# schematic.net
KiCad netlist of a schematic drawn in Altium Designer
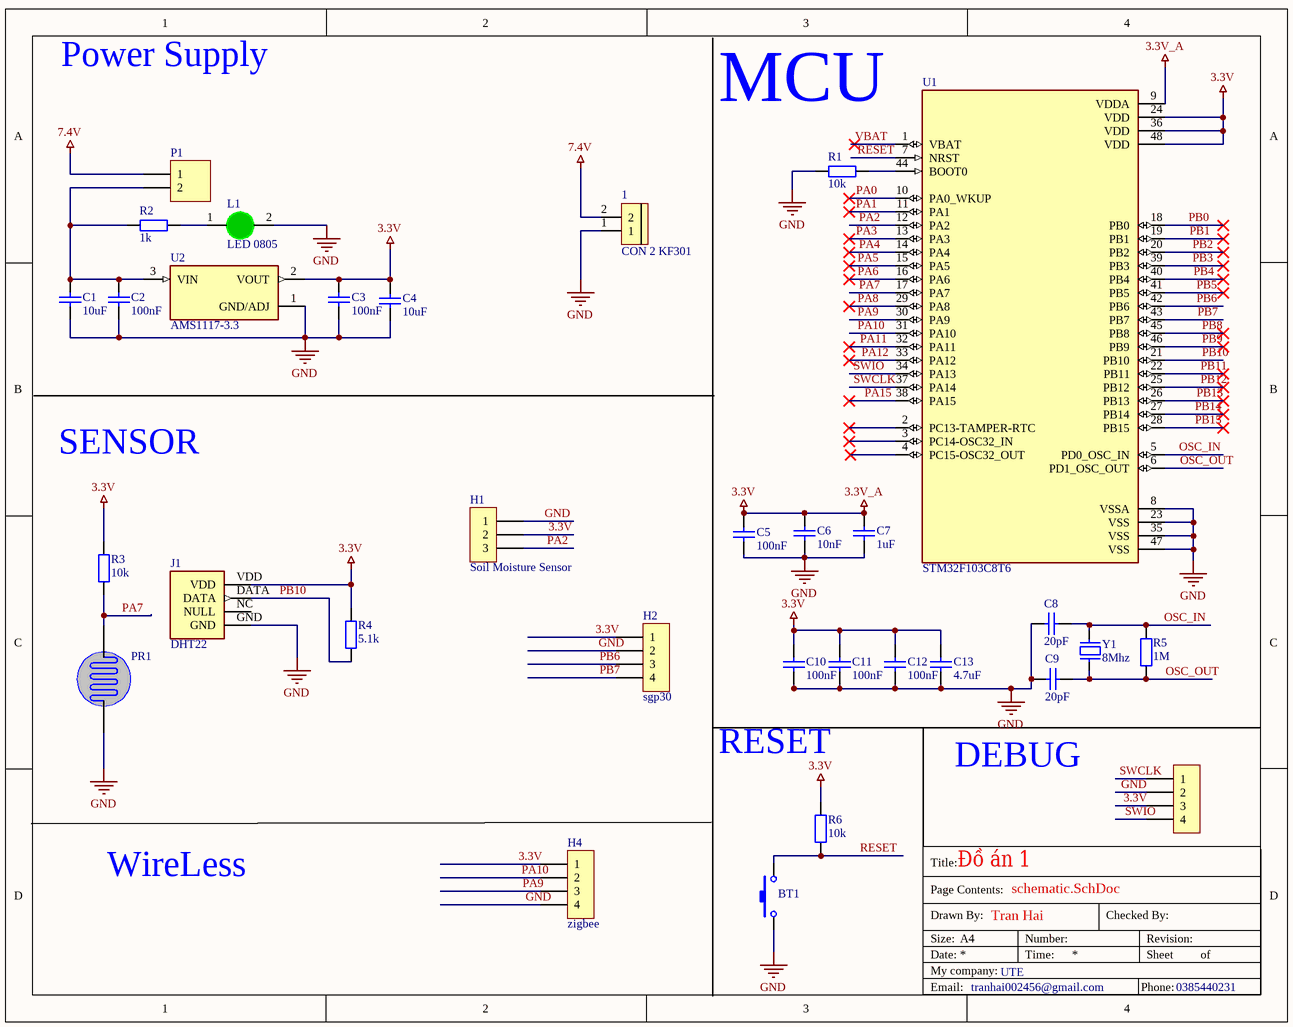
[diagram p0: schematic.SchDoc]

(export (version "E")
  (design (tool "Eeschema 10.0.6"))
  (components
    (comp (ref "1")
      (value "CON 2 KF301")
      (footprint "Con 2 KF301 5.08")
      (description "Cắm")
      (libsource (lib "Altium_Lib_by_KhueNguyenCreator") (part "CON 2 KF301"))
    )
    (comp (ref "BT1")
      (value "Nut Nhan 2 Chan SMD 3x6x2.5")
      (footprint "Nut Nhan 2 Chan SMD 3x6x2.5")
      (libsource (lib "Altium_Lib_by_KhueNguyenCreator") (part "Nut Nhan 2 Chan SMD 3x6x2.5"))
    )
    (comp (ref "C1")
      (value "10uF")
      (footprint "Tu 0805")
      (description "Dán")
      (libsource (lib "Altium_Lib_by_KhueNguyenCreator") (part "Tu 0805 200pF 50V 10%"))
    )
    (comp (ref "C2")
      (value "100nF")
      (footprint "Tu 0805")
      (description "Dán")
      (libsource (lib "Altium_Lib_by_KhueNguyenCreator") (part "Tu 0805 200pF 50V 10%"))
    )
    (comp (ref "C3")
      (value "100nF")
      (footprint "Tu 0805")
      (description "Dán")
      (libsource (lib "Altium_Lib_by_KhueNguyenCreator") (part "Tu 0805 200pF 50V 10%"))
    )
    (comp (ref "C4")
      (value "10uF")
      (footprint "Tu 0805")
      (description "Dán")
      (libsource (lib "Altium_Lib_by_KhueNguyenCreator") (part "Tu 0805 200pF 50V 10%"))
    )
    (comp (ref "C5")
      (value "100nF")
      (footprint "tu 0805")
      (description "Dán")
      (libsource (lib "Altium_Lib_by_KhueNguyenCreator") (part "Tu 0805 101 50V 20%"))
    )
    (comp (ref "C6")
      (value "10nF")
      (footprint "tu 0805")
      (description "Dán")
      (libsource (lib "Altium_Lib_by_KhueNguyenCreator") (part "Tu 0805 101 50V 20%"))
    )
    (comp (ref "C7")
      (value "1uF")
      (footprint "tu 0805")
      (description "Dán")
      (libsource (lib "Altium_Lib_by_KhueNguyenCreator") (part "Tu 0805 101 50V 20%"))
    )
    (comp (ref "C8")
      (value "20pF")
      (footprint "tu 0805")
      (description "Dán")
      (libsource (lib "Altium_Lib_by_KhueNguyenCreator") (part "Tu 0805 101 50V 20%"))
    )
    (comp (ref "C9")
      (value "20pF")
      (footprint "tu 0805")
      (description "Dán")
      (libsource (lib "Altium_Lib_by_KhueNguyenCreator") (part "Tu 0805 101 50V 20%"))
    )
    (comp (ref "C10")
      (value "100nF")
      (footprint "tu 0805")
      (description "Dán")
      (libsource (lib "") (part "Tu 0805 101 50V 20%_1"))
    )
    (comp (ref "C11")
      (value "100nF")
      (footprint "tu 0805")
      (description "Dán")
      (libsource (lib "") (part "Tu 0805 101 50V 20%_1"))
    )
    (comp (ref "C12")
      (value "100nF")
      (footprint "tu 0805")
      (description "Dán")
      (libsource (lib "") (part "Tu 0805 101 50V 20%_1"))
    )
    (comp (ref "C13")
      (value "4.7uF")
      (footprint "tu 0805")
      (description "Dán")
      (libsource (lib "") (part "Tu 0805 101 50V 20%_1"))
    )
    (comp (ref "H1")
      (value "Soil Moisture Sensor")
      (footprint "XH2.54M-3")
      (description "Cắm")
      (libsource (lib "Altium_Lib_by_KhueNguyenCreator") (part "Header 3P 2.54 Duc Thang"))
    )
    (comp (ref "H2")
      (value "sgp30")
      (footprint "XH2.54M-4")
      (description "Cắm")
      (libsource (lib "Altium_Lib_by_KhueNguyenCreator") (part "Header 4P 2.54 Duc Thang"))
    )
    (comp (ref "H3")
      (value "Header 4P 2.54 Duc Thang")
      (footprint "XH2.54M-4")
      (description "Cắm")
      (libsource (lib "Altium_Lib_by_KhueNguyenCreator") (part "Header 4P 2.54 Duc Thang"))
    )
    (comp (ref "H4")
      (value "zigbee")
      (footprint "XH2.54M-4")
      (description "Cắm")
      (libsource (lib "Altium_Lib_by_KhueNguyenCreator") (part "Header 4P 2.54 Duc Thang"))
    )
    (comp (ref "J1")
      (value "DHT22")
      (footprint "DHT22")
      (description "Capacitive-type humidity and temperature module/sensor")
      (fields (field (name "MF") "Aosong Electronics"))
      (libsource (lib "DHT22") (part "DHT22"))
    )
    (comp (ref "L1")
      (value "LED 0805")
      (footprint "LED-0805-Green")
      (description "Dán")
      (libsource (lib "Altium_Lib_by_KhueNguyenCreator") (part "LED 0805 Xanh La"))
    )
    (comp (ref "P1")
      (value "Header 2")
      (footprint "HDR1X2")
      (description "Header, 2-Pin")
      (fields (field (name "PUBLISHER") "Altium Limited"))
      (libsource (lib "Library AL") (part "Header 2"))
    )
    (comp (ref "PR1")
      (value "Quang Tro")
      (footprint "Quang Tro")
      (description "Photoresistor")
      (fields (field (name "CREATOR") "Bien Nguyen"))
      (libsource (lib "Altium_Lib_by_KhueNguyenCreator") (part "Quang Tro"))
    )
    (comp (ref "R1")
      (value "10k")
      (footprint "tro smd 0805")
      (description "Dán")
      (libsource (lib "Altium_Lib_by_KhueNguyenCreator") (part "Tro 0805 1% 10k"))
    )
    (comp (ref "R2")
      (value "1k")
      (footprint "tro smd 0805")
      (description "Dán")
      (libsource (lib "Altium_Lib_by_KhueNguyenCreator") (part "Tro 0805 1% 10k"))
    )
    (comp (ref "R3")
      (value "10k")
      (footprint "tro smd 0805")
      (description "Dán")
      (libsource (lib "Altium_Lib_by_KhueNguyenCreator") (part "Tro 0805 1% 10k"))
    )
    (comp (ref "R4")
      (value "5.1k")
      (footprint "tro smd 0805")
      (description "Dán")
      (libsource (lib "Altium_Lib_by_KhueNguyenCreator") (part "Tro 0805 1% 10k"))
    )
    (comp (ref "R5")
      (value "1M")
      (footprint "tro smd 0805")
      (description "Dán")
      (libsource (lib "Altium_Lib_by_KhueNguyenCreator") (part "Tro 0805 1% 10k"))
    )
    (comp (ref "R6")
      (value "10k")
      (footprint "tro smd 0805")
      (description "Dán")
      (libsource (lib "Altium_Lib_by_KhueNguyenCreator") (part "Tro 0805 1% 10k"))
    )
    (comp (ref "U1")
      (value "STM32F103C8T6")
      (footprint "QFP50P900X900X160-48N")
      (description "ARM® Cortex®-M3 STM32F1 Microcontroller IC 32-Bit 72MHz 64KB (64K x 8) FLASH 48-LQFP (7x7)")
      (fields (field (name "MF") "STMicroelectronics"))
      (libsource (lib "STM32F103C8T6") (part "STM32F103C8T6"))
    )
    (comp (ref "U2")
      (value "AMS1117-3.3")
      (footprint "SOT229P700X180-4N")
      (description "Sot223/Pkg 1-Amp 3.3-Volt Low Drop Out Voltage Regulatator")
      (fields (field (name "MF") "Advanced Monolithic Systems"))
      (libsource (lib "AMS1117-3.3") (part "AMS1117-3.3"))
    )
    (comp (ref "Y1")
      (value "8Mhz")
      (footprint "Thach Anh 2 chan cam")
      (description "Crystal For all Crystal 2pin.")
      (libsource (lib "Altium_Lib_by_KhueNguyenCreator") (part "Thach Anh 2 chan Cam"))
    )
  )
  (nets
    (net (code "1") (name "/OSC_IN") (class "Default")
      (node (ref "C8") (pin "1") (pinfunction "1_1") (pintype "passive"))
      (node (ref "R5") (pin "2") (pinfunction "2_2") (pintype "passive"))
      (node (ref "U1") (pin "5") (pinfunction "PD0_OSC_IN_5") (pintype "bidirectional"))
      (node (ref "Y1") (pin "2") (pinfunction "2_2") (pintype "passive"))
    )
    (net (code "2") (name "/OSC_OUT") (class "Default")
      (node (ref "C9") (pin "1") (pinfunction "1_1") (pintype "passive"))
      (node (ref "R5") (pin "1") (pinfunction "1_1") (pintype "passive"))
      (node (ref "U1") (pin "6") (pinfunction "PD1_OSC_OUT_6") (pintype "bidirectional"))
      (node (ref "Y1") (pin "1") (pinfunction "1_1") (pintype "passive"))
    )
    (net (code "3") (name "/PA0") (class "Default")
      (node (ref "U1") (pin "10") (pinfunction "PA0_WKUP_10") (pintype "bidirectional+no_connect"))
    )
    (net (code "4") (name "/PA1") (class "Default")
      (node (ref "U1") (pin "11") (pinfunction "PA1_11") (pintype "bidirectional+no_connect"))
    )
    (net (code "5") (name "/PA2") (class "Default")
      (node (ref "H1") (pin "3") (pinfunction "3_3") (pintype "passive"))
      (node (ref "U1") (pin "12") (pinfunction "PA2_12") (pintype "bidirectional"))
    )
    (net (code "6") (name "/PA3") (class "Default")
      (node (ref "U1") (pin "13") (pinfunction "PA3_13") (pintype "bidirectional+no_connect"))
    )
    (net (code "7") (name "/PA4") (class "Default")
      (node (ref "U1") (pin "14") (pinfunction "PA4_14") (pintype "bidirectional+no_connect"))
    )
    (net (code "8") (name "/PA5") (class "Default")
      (node (ref "U1") (pin "15") (pinfunction "PA5_15") (pintype "bidirectional+no_connect"))
    )
    (net (code "9") (name "/PA6") (class "Default")
      (node (ref "U1") (pin "16") (pinfunction "PA6_16") (pintype "bidirectional+no_connect"))
    )
    (net (code "10") (name "/PA7") (class "Default")
      (node (ref "PR1") (pin "1") (pinfunction "1_1") (pintype "passive"))
      (node (ref "R3") (pin "1") (pinfunction "1_1") (pintype "passive"))
      (node (ref "U1") (pin "17") (pinfunction "PA7_17") (pintype "bidirectional"))
    )
    (net (code "11") (name "/PA8") (class "Default")
      (node (ref "U1") (pin "29") (pinfunction "PA8_29") (pintype "bidirectional+no_connect"))
    )
    (net (code "12") (name "/PA9") (class "Default")
      (node (ref "H4") (pin "3") (pinfunction "3_3") (pintype "passive"))
      (node (ref "U1") (pin "30") (pinfunction "PA9_30") (pintype "bidirectional"))
    )
    (net (code "13") (name "/PA10") (class "Default")
      (node (ref "H4") (pin "2") (pinfunction "2_2") (pintype "passive"))
      (node (ref "U1") (pin "31") (pinfunction "PA10_31") (pintype "bidirectional"))
    )
    (net (code "14") (name "/PA11") (class "Default")
      (node (ref "U1") (pin "32") (pinfunction "PA11_32") (pintype "bidirectional+no_connect"))
    )
    (net (code "15") (name "/PA12") (class "Default")
      (node (ref "U1") (pin "33") (pinfunction "PA12_33") (pintype "bidirectional+no_connect"))
    )
    (net (code "16") (name "/PA15") (class "Default")
      (node (ref "U1") (pin "38") (pinfunction "PA15_38") (pintype "bidirectional+no_connect"))
    )
    (net (code "17") (name "/PB0") (class "Default")
      (node (ref "U1") (pin "18") (pinfunction "PB0_18") (pintype "bidirectional+no_connect"))
    )
    (net (code "18") (name "/PB1") (class "Default")
      (node (ref "U1") (pin "19") (pinfunction "PB1_19") (pintype "bidirectional+no_connect"))
    )
    (net (code "19") (name "/PB2") (class "Default")
      (node (ref "U1") (pin "20") (pinfunction "PB2_20") (pintype "bidirectional+no_connect"))
    )
    (net (code "20") (name "/PB3") (class "Default")
      (node (ref "U1") (pin "39") (pinfunction "PB3_39") (pintype "bidirectional+no_connect"))
    )
    (net (code "21") (name "/PB4") (class "Default")
      (node (ref "U1") (pin "40") (pinfunction "PB4_40") (pintype "bidirectional+no_connect"))
    )
    (net (code "22") (name "/PB5") (class "Default")
      (node (ref "U1") (pin "41") (pinfunction "PB5_41") (pintype "bidirectional+no_connect"))
    )
    (net (code "23") (name "/PB6") (class "Default")
      (node (ref "H2") (pin "3") (pinfunction "3_3") (pintype "passive"))
      (node (ref "U1") (pin "42") (pinfunction "PB6_42") (pintype "bidirectional"))
    )
    (net (code "24") (name "/PB7") (class "Default")
      (node (ref "H2") (pin "4") (pinfunction "4_4") (pintype "passive"))
      (node (ref "U1") (pin "43") (pinfunction "PB7_43") (pintype "bidirectional"))
    )
    (net (code "25") (name "/PB8") (class "Default")
      (node (ref "U1") (pin "45") (pinfunction "PB8_45") (pintype "bidirectional+no_connect"))
    )
    (net (code "26") (name "/PB9") (class "Default")
      (node (ref "U1") (pin "46") (pinfunction "PB9_46") (pintype "bidirectional+no_connect"))
    )
    (net (code "27") (name "/PB10") (class "Default")
      (node (ref "J1") (pin "DATA") (pinfunction "DATA_DATA") (pintype "output"))
      (node (ref "R4") (pin "1") (pinfunction "1_1") (pintype "passive"))
      (node (ref "U1") (pin "21") (pinfunction "PB10_21") (pintype "bidirectional"))
    )
    (net (code "28") (name "/PB11") (class "Default")
      (node (ref "U1") (pin "22") (pinfunction "PB11_22") (pintype "bidirectional+no_connect"))
    )
    (net (code "29") (name "/PB12") (class "Default")
      (node (ref "U1") (pin "25") (pinfunction "PB12_25") (pintype "bidirectional+no_connect"))
    )
    (net (code "30") (name "/PB13") (class "Default")
      (node (ref "U1") (pin "26") (pinfunction "PB13_26") (pintype "bidirectional+no_connect"))
    )
    (net (code "31") (name "/PB14") (class "Default")
      (node (ref "U1") (pin "27") (pinfunction "PB14_27") (pintype "bidirectional+no_connect"))
    )
    (net (code "32") (name "/PB15") (class "Default")
      (node (ref "U1") (pin "28") (pinfunction "PB15_28") (pintype "bidirectional+no_connect"))
    )
    (net (code "33") (name "/RESET") (class "Default")
      (node (ref "BT1") (pin "2") (pinfunction "2_2") (pintype "passive"))
      (node (ref "R6") (pin "1") (pinfunction "1_1") (pintype "passive"))
      (node (ref "U1") (pin "7") (pinfunction "NRST_7") (pintype "input"))
    )
    (net (code "34") (name "/SWCLK") (class "Default")
      (node (ref "H3") (pin "1") (pinfunction "1_1") (pintype "passive"))
      (node (ref "U1") (pin "37") (pinfunction "PA14_37") (pintype "bidirectional"))
    )
    (net (code "35") (name "/SWIO") (class "Default")
      (node (ref "H3") (pin "4") (pinfunction "4_4") (pintype "passive"))
      (node (ref "U1") (pin "34") (pinfunction "PA13_34") (pintype "bidirectional"))
    )
    (net (code "37") (name "/VBAT") (class "Default")
      (node (ref "U1") (pin "1") (pinfunction "VBAT_1") (pintype "bidirectional"))
    )
    (net (code "38") (name "3.3V") (class "Default")
      (node (ref "C10") (pin "1") (pinfunction "1_1") (pintype "passive"))
      (node (ref "C11") (pin "1") (pinfunction "1_1") (pintype "passive"))
      (node (ref "C12") (pin "1") (pinfunction "1_1") (pintype "passive"))
      (node (ref "C13") (pin "1") (pinfunction "1_1") (pintype "passive"))
      (node (ref "C3") (pin "1") (pinfunction "1_1") (pintype "passive"))
      (node (ref "C4") (pin "1") (pinfunction "1_1") (pintype "passive"))
      (node (ref "C5") (pin "1") (pinfunction "1_1") (pintype "passive"))
      (node (ref "C6") (pin "1") (pinfunction "1_1") (pintype "passive"))
      (node (ref "C7") (pin "1") (pinfunction "1_1") (pintype "passive"))
      (node (ref "H1") (pin "2") (pinfunction "2_2") (pintype "passive"))
      (node (ref "H2") (pin "1") (pinfunction "1_1") (pintype "passive"))
      (node (ref "H3") (pin "3") (pinfunction "3_3") (pintype "passive"))
      (node (ref "H4") (pin "1") (pinfunction "1_1") (pintype "passive"))
      (node (ref "J1") (pin "VDD") (pinfunction "VDD_VDD") (pintype "power_in"))
      (node (ref "R3") (pin "2") (pinfunction "2_2") (pintype "passive"))
      (node (ref "R4") (pin "2") (pinfunction "2_2") (pintype "passive"))
      (node (ref "R6") (pin "2") (pinfunction "2_2") (pintype "passive"))
      (node (ref "U1") (pin "24") (pinfunction "VDD_24") (pintype "power_in"))
      (node (ref "U1") (pin "36") (pinfunction "VDD_36") (pintype "power_in"))
      (node (ref "U1") (pin "48") (pinfunction "VDD_48") (pintype "power_in"))
      (node (ref "U1") (pin "9") (pinfunction "VDDA_9") (pintype "power_in"))
      (node (ref "U2") (pin "2") (pinfunction "VOUT_2") (pintype "output"))
    )
    (net (code "39") (name "7.4V") (class "Default")
      (node (ref "1") (pin "2") (pinfunction "2_2") (pintype "passive"))
      (node (ref "P1") (pin "1") (pinfunction "1_1") (pintype "passive"))
    )
    (net (code "40") (name "GND") (class "Default")
      (node (ref "1") (pin "1") (pinfunction "1_1") (pintype "passive"))
      (node (ref "BT1") (pin "1") (pinfunction "1_1") (pintype "passive"))
      (node (ref "C1") (pin "2") (pinfunction "2_2") (pintype "passive"))
      (node (ref "C10") (pin "2") (pinfunction "2_2") (pintype "passive"))
      (node (ref "C11") (pin "2") (pinfunction "2_2") (pintype "passive"))
      (node (ref "C12") (pin "2") (pinfunction "2_2") (pintype "passive"))
      (node (ref "C13") (pin "2") (pinfunction "2_2") (pintype "passive"))
      (node (ref "C2") (pin "2") (pinfunction "2_2") (pintype "passive"))
      (node (ref "C3") (pin "2") (pinfunction "2_2") (pintype "passive"))
      (node (ref "C4") (pin "2") (pinfunction "2_2") (pintype "passive"))
      (node (ref "C5") (pin "2") (pinfunction "2_2") (pintype "passive"))
      (node (ref "C6") (pin "2") (pinfunction "2_2") (pintype "passive"))
      (node (ref "C7") (pin "2") (pinfunction "2_2") (pintype "passive"))
      (node (ref "C8") (pin "2") (pinfunction "2_2") (pintype "passive"))
      (node (ref "C9") (pin "2") (pinfunction "2_2") (pintype "passive"))
      (node (ref "H1") (pin "1") (pinfunction "1_1") (pintype "passive"))
      (node (ref "H2") (pin "2") (pinfunction "2_2") (pintype "passive"))
      (node (ref "H3") (pin "2") (pinfunction "2_2") (pintype "passive"))
      (node (ref "H4") (pin "4") (pinfunction "4_4") (pintype "passive"))
      (node (ref "J1") (pin "GND") (pinfunction "GND_GND") (pintype "power_in"))
      (node (ref "L1") (pin "2") (pinfunction "K_2") (pintype "passive"))
      (node (ref "PR1") (pin "2") (pinfunction "2_2") (pintype "passive"))
      (node (ref "R1") (pin "1") (pinfunction "1_1") (pintype "passive"))
      (node (ref "U1") (pin "23") (pinfunction "VSS_23") (pintype "power_in"))
      (node (ref "U1") (pin "35") (pinfunction "VSS_35") (pintype "power_in"))
      (node (ref "U1") (pin "47") (pinfunction "VSS_47") (pintype "power_in"))
      (node (ref "U1") (pin "8") (pinfunction "VSSA_8") (pintype "power_in"))
      (node (ref "U2") (pin "1") (pinfunction "GND/ADJ_1") (pintype "power_in"))
    )
    (net (code "41") (name "Net-(L1-A)") (class "Default")
      (node (ref "L1") (pin "1") (pinfunction "A_1") (pintype "passive"))
      (node (ref "R2") (pin "2") (pinfunction "2_2") (pintype "passive"))
    )
    (net (code "42") (name "Net-(U1-BOOT0)") (class "Default")
      (node (ref "R1") (pin "2") (pinfunction "2_2") (pintype "passive"))
      (node (ref "U1") (pin "44") (pinfunction "BOOT0_44") (pintype "input"))
    )
    (net (code "43") (name "Net-(U2-VIN)") (class "Default")
      (node (ref "C1") (pin "1") (pinfunction "1_1") (pintype "passive"))
      (node (ref "C2") (pin "1") (pinfunction "1_1") (pintype "passive"))
      (node (ref "P1") (pin "2") (pinfunction "2_2") (pintype "passive"))
      (node (ref "R2") (pin "1") (pinfunction "1_1") (pintype "passive"))
      (node (ref "U2") (pin "3") (pinfunction "VIN_3") (pintype "input"))
    )
    (net (code "44") (name "unconnected-(J1-NULL-PadNC)") (class "Default")
      (node (ref "J1") (pin "NC") (pinfunction "NULL_NC") (pintype "passive"))
    )
    (net (code "45") (name "unconnected-(U1-PC13-TAMPER-RTC-Pad2)") (class "Default")
      (node (ref "U1") (pin "2") (pinfunction "PC13-TAMPER-RTC_2") (pintype "bidirectional+no_connect"))
    )
    (net (code "46") (name "unconnected-(U1-PC14-OSC32_IN-Pad3)") (class "Default")
      (node (ref "U1") (pin "3") (pinfunction "PC14-OSC32_IN_3") (pintype "bidirectional+no_connect"))
    )
    (net (code "47") (name "unconnected-(U1-PC15-OSC32_OUT-Pad4)") (class "Default")
      (node (ref "U1") (pin "4") (pinfunction "PC15-OSC32_OUT_4") (pintype "bidirectional+no_connect"))
    )
  )
)
